# Kube_LoRaWAN_Module.net
KiCad netlist of a schematic drawn in EAGLE
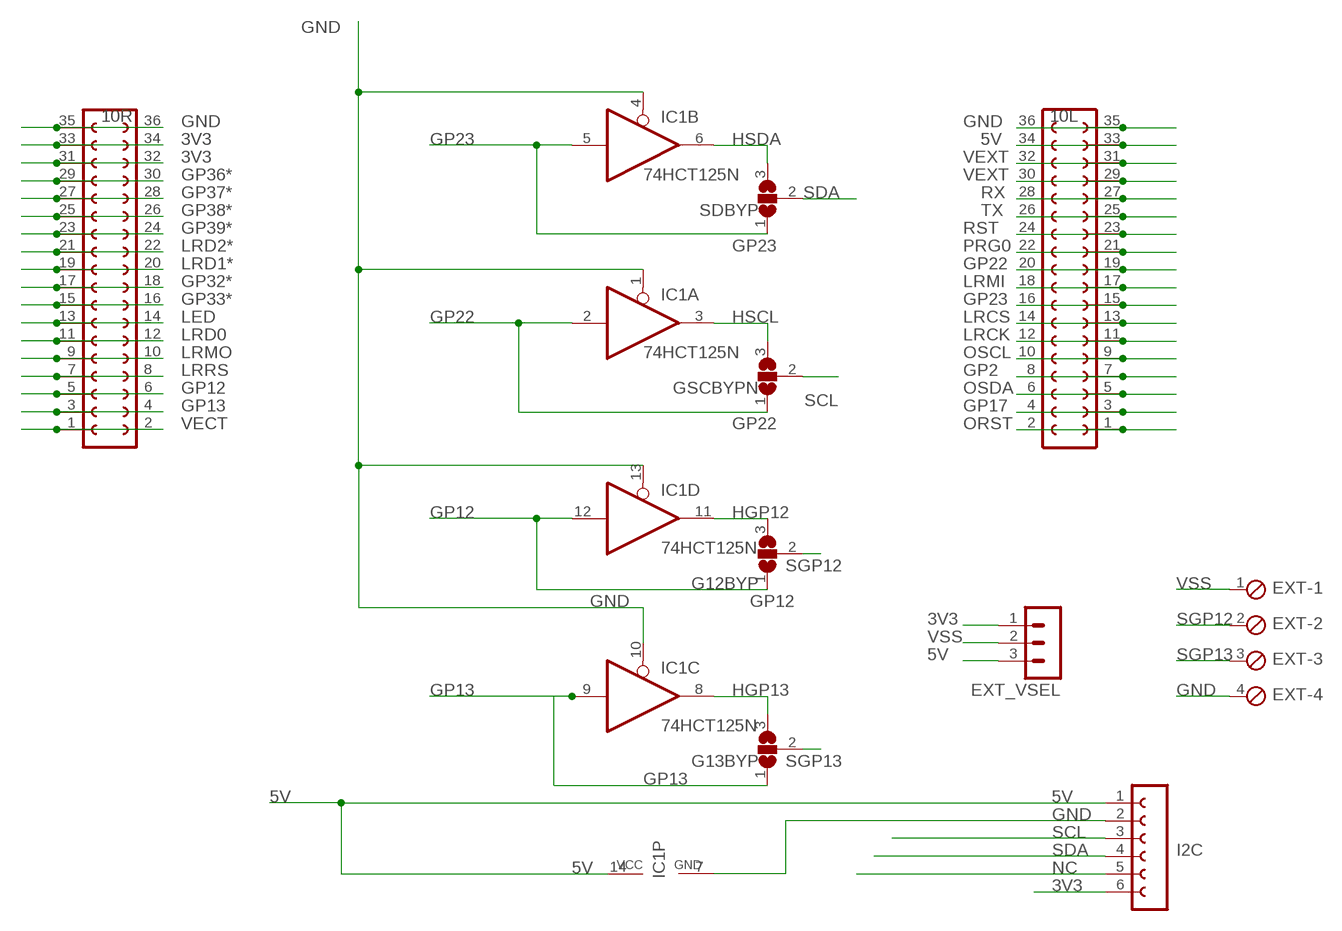
[diagram p0: schematic, sheet 1]

(export (version "E")
  (design (tool "Eeschema 10.0.6"))
  (components
    (comp (ref "10L")
      (value "15")
      (footprint "eagle-import:FE18-2")
      (libsource (lib "eagle-import") (part "FE18-2"))
    )
    (comp (ref "10R")
      (value "15")
      (footprint "eagle-import:FE18-2")
      (libsource (lib "eagle-import") (part "FE18-2"))
    )
    (comp (ref "EXT")
      (value "MPT4")
      (footprint "eagle-import:4POL254")
      (libsource (lib "eagle-import") (part "MPT4"))
    )
    (comp (ref "EXT_VSEL")
      (value "MA03-1")
      (footprint "eagle-import:MA03-1")
      (libsource (lib "eagle-import") (part "MA03-1"))
    )
    (comp (ref "G12BYP")
      (value "SJ2W")
      (footprint "eagle-import:SJ_2")
      (libsource (lib "eagle-import") (part "SJ2W"))
    )
    (comp (ref "G13BYP")
      (value "SJ2W")
      (footprint "eagle-import:SJ_2")
      (libsource (lib "eagle-import") (part "SJ2W"))
    )
    (comp (ref "GSCBYPN")
      (value "SJ2W")
      (footprint "eagle-import:SJ_2")
      (libsource (lib "eagle-import") (part "SJ2W"))
    )
    (comp (ref "I2C")
      (value "FE06-1")
      (footprint "eagle-import:FE06")
      (libsource (lib "eagle-import") (part "FE06-1"))
    )
    (comp (ref "IC1")
      (value "74HCT125N")
      (footprint "eagle-import:DIL14")
      (libsource (lib "eagle-import") (part "74125NHCT"))
    )
    (comp (ref "SDBYP")
      (value "SJ2W")
      (footprint "eagle-import:SJ_2")
      (libsource (lib "eagle-import") (part "SJ2W"))
    )
  )
  (nets
    (net (code "1") (name "/3V3") (class "Default")
      (node (ref "10R") (pin "31") (pinfunction "31_31") (pintype "passive"))
      (node (ref "10R") (pin "32") (pinfunction "32_32") (pintype "passive"))
      (node (ref "10R") (pin "33") (pinfunction "33_33") (pintype "passive"))
      (node (ref "10R") (pin "34") (pinfunction "34_34") (pintype "passive"))
      (node (ref "EXT_VSEL") (pin "1") (pinfunction "1_1") (pintype "passive"))
      (node (ref "I2C") (pin "6") (pinfunction "6_6") (pintype "passive"))
    )
    (net (code "2") (name "/5V") (class "Default")
      (node (ref "10L") (pin "33") (pinfunction "33_33") (pintype "passive"))
      (node (ref "10L") (pin "34") (pinfunction "34_34") (pintype "passive"))
      (node (ref "EXT_VSEL") (pin "3") (pinfunction "3_3") (pintype "passive"))
      (node (ref "I2C") (pin "1") (pinfunction "1_1") (pintype "passive"))
      (node (ref "IC1") (pin "14") (pinfunction "VCC_14") (pintype "power_in"))
    )
    (net (code "3") (name "/GND") (class "Default")
      (node (ref "10L") (pin "35") (pinfunction "35_35") (pintype "passive"))
      (node (ref "10L") (pin "36") (pinfunction "36_36") (pintype "passive"))
      (node (ref "10R") (pin "35") (pinfunction "35_35") (pintype "passive"))
      (node (ref "10R") (pin "36") (pinfunction "36_36") (pintype "passive"))
      (node (ref "EXT") (pin "4") (pinfunction "1_4") (pintype "passive"))
      (node (ref "I2C") (pin "2") (pinfunction "2_2") (pintype "passive"))
      (node (ref "IC1") (pin "1") (pinfunction "OE_1") (pintype "input"))
      (node (ref "IC1") (pin "10") (pinfunction "OE_10") (pintype "input"))
      (node (ref "IC1") (pin "13") (pinfunction "OE_13") (pintype "input"))
      (node (ref "IC1") (pin "4") (pinfunction "OE_4") (pintype "input"))
      (node (ref "IC1") (pin "7") (pinfunction "GND_7") (pintype "power_in"))
    )
    (net (code "4") (name "/GP2") (class "Default")
      (node (ref "10L") (pin "7") (pinfunction "7_7") (pintype "passive"))
      (node (ref "10L") (pin "8") (pinfunction "8_8") (pintype "passive"))
    )
    (net (code "5") (name "/GP12") (class "Default")
      (node (ref "10R") (pin "5") (pinfunction "5_5") (pintype "passive"))
      (node (ref "10R") (pin "6") (pinfunction "6_6") (pintype "passive"))
      (node (ref "G12BYP") (pin "1") (pinfunction "1_1") (pintype "passive"))
      (node (ref "IC1") (pin "12") (pinfunction "I_12") (pintype "input"))
    )
    (net (code "6") (name "/GP13") (class "Default")
      (node (ref "10R") (pin "3") (pinfunction "3_3") (pintype "passive"))
      (node (ref "10R") (pin "4") (pinfunction "4_4") (pintype "passive"))
      (node (ref "G13BYP") (pin "1") (pinfunction "1_1") (pintype "passive"))
      (node (ref "IC1") (pin "9") (pinfunction "I_9") (pintype "input"))
    )
    (net (code "7") (name "/GP17") (class "Default")
      (node (ref "10L") (pin "3") (pinfunction "3_3") (pintype "passive"))
      (node (ref "10L") (pin "4") (pinfunction "4_4") (pintype "passive"))
    )
    (net (code "8") (name "/GP22") (class "Default")
      (node (ref "10L") (pin "19") (pinfunction "19_19") (pintype "passive"))
      (node (ref "10L") (pin "20") (pinfunction "20_20") (pintype "passive"))
      (node (ref "GSCBYPN") (pin "1") (pinfunction "1_1") (pintype "passive"))
      (node (ref "IC1") (pin "2") (pinfunction "I_2") (pintype "input"))
    )
    (net (code "9") (name "/GP23") (class "Default")
      (node (ref "10L") (pin "15") (pinfunction "15_15") (pintype "passive"))
      (node (ref "10L") (pin "16") (pinfunction "16_16") (pintype "passive"))
      (node (ref "IC1") (pin "5") (pinfunction "I_5") (pintype "input"))
      (node (ref "SDBYP") (pin "1") (pinfunction "1_1") (pintype "passive"))
    )
    (net (code "10") (name "/GP32*") (class "Default")
      (node (ref "10R") (pin "17") (pinfunction "17_17") (pintype "passive"))
      (node (ref "10R") (pin "18") (pinfunction "18_18") (pintype "passive"))
    )
    (net (code "11") (name "/GP33*") (class "Default")
      (node (ref "10R") (pin "15") (pinfunction "15_15") (pintype "passive"))
      (node (ref "10R") (pin "16") (pinfunction "16_16") (pintype "passive"))
    )
    (net (code "12") (name "/GP36*") (class "Default")
      (node (ref "10R") (pin "29") (pinfunction "29_29") (pintype "passive"))
      (node (ref "10R") (pin "30") (pinfunction "30_30") (pintype "passive"))
    )
    (net (code "13") (name "/GP37*") (class "Default")
      (node (ref "10R") (pin "27") (pinfunction "27_27") (pintype "passive"))
      (node (ref "10R") (pin "28") (pinfunction "28_28") (pintype "passive"))
    )
    (net (code "14") (name "/GP38*") (class "Default")
      (node (ref "10R") (pin "25") (pinfunction "25_25") (pintype "passive"))
      (node (ref "10R") (pin "26") (pinfunction "26_26") (pintype "passive"))
    )
    (net (code "15") (name "/GP39*") (class "Default")
      (node (ref "10R") (pin "23") (pinfunction "23_23") (pintype "passive"))
      (node (ref "10R") (pin "24") (pinfunction "24_24") (pintype "passive"))
    )
    (net (code "16") (name "/HGP12") (class "Default")
      (node (ref "G12BYP") (pin "3") (pinfunction "3_3") (pintype "passive"))
      (node (ref "IC1") (pin "11") (pinfunction "O_11") (pintype "tri_state"))
    )
    (net (code "17") (name "/HGP13") (class "Default")
      (node (ref "G13BYP") (pin "3") (pinfunction "3_3") (pintype "passive"))
      (node (ref "IC1") (pin "8") (pinfunction "O_8") (pintype "tri_state"))
    )
    (net (code "18") (name "/HSCL") (class "Default")
      (node (ref "GSCBYPN") (pin "3") (pinfunction "3_3") (pintype "passive"))
      (node (ref "IC1") (pin "3") (pinfunction "O_3") (pintype "tri_state"))
    )
    (net (code "19") (name "/HSDA") (class "Default")
      (node (ref "IC1") (pin "6") (pinfunction "O_6") (pintype "tri_state"))
      (node (ref "SDBYP") (pin "3") (pinfunction "3_3") (pintype "passive"))
    )
    (net (code "20") (name "/LED") (class "Default")
      (node (ref "10R") (pin "13") (pinfunction "13_13") (pintype "passive"))
      (node (ref "10R") (pin "14") (pinfunction "14_14") (pintype "passive"))
    )
    (net (code "21") (name "/LRCK") (class "Default")
      (node (ref "10L") (pin "11") (pinfunction "11_11") (pintype "passive"))
      (node (ref "10L") (pin "12") (pinfunction "12_12") (pintype "passive"))
    )
    (net (code "22") (name "/LRCS") (class "Default")
      (node (ref "10L") (pin "13") (pinfunction "13_13") (pintype "passive"))
      (node (ref "10L") (pin "14") (pinfunction "14_14") (pintype "passive"))
    )
    (net (code "23") (name "/LRD0") (class "Default")
      (node (ref "10R") (pin "11") (pinfunction "11_11") (pintype "passive"))
      (node (ref "10R") (pin "12") (pinfunction "12_12") (pintype "passive"))
    )
    (net (code "24") (name "/LRD1*") (class "Default")
      (node (ref "10R") (pin "19") (pinfunction "19_19") (pintype "passive"))
      (node (ref "10R") (pin "20") (pinfunction "20_20") (pintype "passive"))
    )
    (net (code "25") (name "/LRD2*") (class "Default")
      (node (ref "10R") (pin "21") (pinfunction "21_21") (pintype "passive"))
      (node (ref "10R") (pin "22") (pinfunction "22_22") (pintype "passive"))
    )
    (net (code "26") (name "/LRMI") (class "Default")
      (node (ref "10L") (pin "17") (pinfunction "17_17") (pintype "passive"))
      (node (ref "10L") (pin "18") (pinfunction "18_18") (pintype "passive"))
    )
    (net (code "27") (name "/LRMO") (class "Default")
      (node (ref "10R") (pin "10") (pinfunction "10_10") (pintype "passive"))
      (node (ref "10R") (pin "9") (pinfunction "9_9") (pintype "passive"))
    )
    (net (code "28") (name "/LRRS") (class "Default")
      (node (ref "10R") (pin "7") (pinfunction "7_7") (pintype "passive"))
      (node (ref "10R") (pin "8") (pinfunction "8_8") (pintype "passive"))
    )
    (net (code "29") (name "/NC") (class "Default")
      (node (ref "I2C") (pin "5") (pinfunction "5_5") (pintype "passive"))
    )
    (net (code "30") (name "/ORST") (class "Default")
      (node (ref "10L") (pin "1") (pinfunction "1_1") (pintype "passive"))
      (node (ref "10L") (pin "2") (pinfunction "2_2") (pintype "passive"))
    )
    (net (code "31") (name "/OSCL") (class "Default")
      (node (ref "10L") (pin "10") (pinfunction "10_10") (pintype "passive"))
      (node (ref "10L") (pin "9") (pinfunction "9_9") (pintype "passive"))
    )
    (net (code "32") (name "/OSDA") (class "Default")
      (node (ref "10L") (pin "5") (pinfunction "5_5") (pintype "passive"))
      (node (ref "10L") (pin "6") (pinfunction "6_6") (pintype "passive"))
    )
    (net (code "33") (name "/PRG0") (class "Default")
      (node (ref "10L") (pin "21") (pinfunction "21_21") (pintype "passive"))
      (node (ref "10L") (pin "22") (pinfunction "22_22") (pintype "passive"))
    )
    (net (code "34") (name "/RST") (class "Default")
      (node (ref "10L") (pin "23") (pinfunction "23_23") (pintype "passive"))
      (node (ref "10L") (pin "24") (pinfunction "24_24") (pintype "passive"))
    )
    (net (code "35") (name "/RX") (class "Default")
      (node (ref "10L") (pin "27") (pinfunction "27_27") (pintype "passive"))
      (node (ref "10L") (pin "28") (pinfunction "28_28") (pintype "passive"))
    )
    (net (code "36") (name "/SCL") (class "Default")
      (node (ref "GSCBYPN") (pin "2") (pinfunction "2_2") (pintype "passive"))
      (node (ref "I2C") (pin "3") (pinfunction "3_3") (pintype "passive"))
    )
    (net (code "37") (name "/SDA") (class "Default")
      (node (ref "I2C") (pin "4") (pinfunction "4_4") (pintype "passive"))
      (node (ref "SDBYP") (pin "2") (pinfunction "2_2") (pintype "passive"))
    )
    (net (code "38") (name "/SGP12") (class "Default")
      (node (ref "EXT") (pin "2") (pinfunction "1_2") (pintype "passive"))
      (node (ref "G12BYP") (pin "2") (pinfunction "2_2") (pintype "passive"))
    )
    (net (code "39") (name "/SGP13") (class "Default")
      (node (ref "EXT") (pin "3") (pinfunction "1_3") (pintype "passive"))
      (node (ref "G13BYP") (pin "2") (pinfunction "2_2") (pintype "passive"))
    )
    (net (code "40") (name "/TX") (class "Default")
      (node (ref "10L") (pin "25") (pinfunction "25_25") (pintype "passive"))
      (node (ref "10L") (pin "26") (pinfunction "26_26") (pintype "passive"))
    )
    (net (code "41") (name "/VECT") (class "Default")
      (node (ref "10R") (pin "1") (pinfunction "1_1") (pintype "passive"))
      (node (ref "10R") (pin "2") (pinfunction "2_2") (pintype "passive"))
    )
    (net (code "42") (name "/VEXT") (class "Default")
      (node (ref "10L") (pin "29") (pinfunction "29_29") (pintype "passive"))
      (node (ref "10L") (pin "30") (pinfunction "30_30") (pintype "passive"))
      (node (ref "10L") (pin "31") (pinfunction "31_31") (pintype "passive"))
      (node (ref "10L") (pin "32") (pinfunction "32_32") (pintype "passive"))
    )
    (net (code "43") (name "/VSS") (class "Default")
      (node (ref "EXT") (pin "1") (pinfunction "1_1") (pintype "passive"))
      (node (ref "EXT_VSEL") (pin "2") (pinfunction "2_2") (pintype "passive"))
    )
  )
)
